# Connectors.net
KiCad netlist of a schematic drawn in Altium Designer
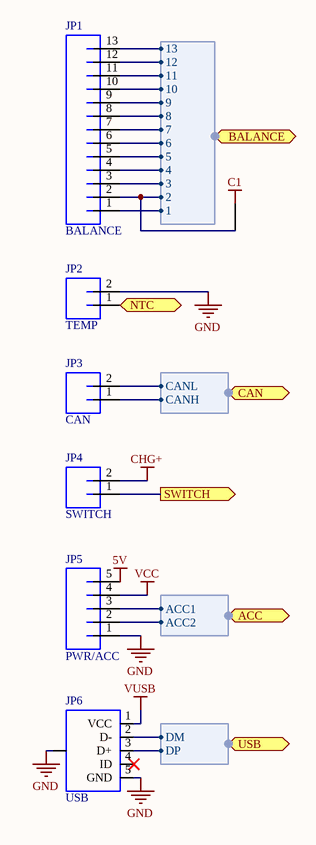
[diagram p0: Connectors.SchDoc]

(export (version "E")
  (design (tool "Eeschema 10.0.6"))
  (components
    (comp (ref "*1") (value "NetTie") (footprint "NetTie") (libsource (lib "Components") (part "NetTie")))
    (comp (ref "JP1")
      (value "BALANCE")
      (footprint "JST-XH-13-PTH-VERT")
      (fields
        (field (name "MANUFACTURER") "JST Sales America, Inc.")
        (field (name "PARTNUMBER") "B13B-XH-A(LF)(SN)")
      )
      (libsource (lib "Connectors-JST") (part "JST_XH_13_VERT"))
    )
    (comp (ref "JP2")
      (value "TEMP")
      (footprint "JST-PH-2-PTH-VERT")
      (fields
        (field (name "MANUFACTURER") "JST Sales America, Inc.")
        (field (name "PARTNUMBER") "B2B-PH-K-S(LF)(SN)")
      )
      (libsource (lib "Connectors") (part "JST_PH_2_VERT"))
    )
    (comp (ref "JP3")
      (value "CAN")
      (footprint "JST-PH-2-PTH-VERT")
      (fields
        (field (name "MANUFACTURER") "JST Sales America, Inc.")
        (field (name "PARTNUMBER") "B2B-PH-K-S(LF)(SN)")
      )
      (libsource (lib "Connectors") (part "JST_PH_2_VERT"))
    )
    (comp (ref "JP4")
      (value "SWITCH")
      (footprint "JST-PH-2-PTH-VERT")
      (fields
        (field (name "MANUFACTURER") "JST Sales America, Inc.")
        (field (name "PARTNUMBER") "B2B-PH-K-S(LF)(SN)")
      )
      (libsource (lib "Connectors") (part "JST_PH_2_VERT"))
    )
    (comp (ref "JP5")
      (value "PWR/ACC")
      (footprint "JST-PH-5-PTH-VERT")
      (fields
        (field (name "MANUFACTURER") "JST Sales America, Inc.")
        (field (name "PARTNUMBER") "B5B-PH-K-S(LF)(SN)")
      )
      (libsource (lib "Connectors") (part "JST_PH_5_VERT"))
    )
    (comp (ref "JP6")
      (value "USB")
      (footprint "USB-MICROB")
      (fields (field (name "PARTNUMBER") "10118192-0001LF") (field (name "MANUFACTURER") "Amphenol FCI"))
      (libsource (lib "Connectors") (part "USB_MICROB_SMT"))
    )
  )
  (nets
    (net (code "7") (name "/1") (class "Default")
      (node (ref "JP1") (pin "1") (pinfunction "1_1") (pintype "passive"))
    )
    (net (code "8") (name "/2") (class "Default")
      (node (ref "*1") (pin "1") (pinfunction "1_1") (pintype "passive"))
      (node (ref "JP1") (pin "2") (pinfunction "2_2") (pintype "passive"))
    )
    (net (code "9") (name "/3") (class "Default")
      (node (ref "JP1") (pin "3") (pinfunction "3_3") (pintype "passive"))
    )
    (net (code "10") (name "/4") (class "Default")
      (node (ref "JP1") (pin "4") (pinfunction "4_4") (pintype "passive"))
    )
    (net (code "11") (name "/5") (class "Default")
      (node (ref "JP1") (pin "5") (pinfunction "5_5") (pintype "passive"))
    )
    (net (code "12") (name "/6") (class "Default")
      (node (ref "JP1") (pin "6") (pinfunction "6_6") (pintype "passive"))
    )
    (net (code "13") (name "/7") (class "Default")
      (node (ref "JP1") (pin "7") (pinfunction "7_7") (pintype "passive"))
    )
    (net (code "14") (name "/8") (class "Default")
      (node (ref "JP1") (pin "8") (pinfunction "8_8") (pintype "passive"))
    )
    (net (code "15") (name "/9") (class "Default")
      (node (ref "JP1") (pin "9") (pinfunction "9_9") (pintype "passive"))
    )
    (net (code "16") (name "/10") (class "Default")
      (node (ref "JP1") (pin "10") (pinfunction "10_10") (pintype "passive"))
    )
    (net (code "17") (name "/11") (class "Default")
      (node (ref "JP1") (pin "11") (pinfunction "11_11") (pintype "passive"))
    )
    (net (code "18") (name "/12") (class "Default")
      (node (ref "JP1") (pin "12") (pinfunction "12_12") (pintype "passive"))
    )
    (net (code "19") (name "/13") (class "Default")
      (node (ref "JP1") (pin "13") (pinfunction "13_13") (pintype "passive"))
    )
    (net (code "20") (name "/ACC1") (class "Default")
      (node (ref "JP5") (pin "3") (pinfunction "3_3") (pintype "passive"))
    )
    (net (code "21") (name "/ACC2") (class "Default")
      (node (ref "JP5") (pin "2") (pinfunction "2_2") (pintype "passive"))
    )
    (net (code "22") (name "/CANH") (class "Default")
      (node (ref "JP3") (pin "1") (pinfunction "1_1") (pintype "passive"))
    )
    (net (code "23") (name "/CANL") (class "Default")
      (node (ref "JP3") (pin "2") (pinfunction "2_2") (pintype "passive"))
    )
    (net (code "24") (name "/DM") (class "Default")
      (node (ref "JP6") (pin "2") (pinfunction "D-_2") (pintype "passive"))
    )
    (net (code "25") (name "/DP") (class "Default")
      (node (ref "JP6") (pin "3") (pinfunction "D+_3") (pintype "passive"))
    )
    (net (code "26") (name "/NTC") (class "Default")
      (node (ref "JP2") (pin "1") (pinfunction "1_1") (pintype "passive"))
    )
    (net (code "27") (name "/SWITCH") (class "Default")
      (node (ref "JP4") (pin "1") (pinfunction "1_1") (pintype "passive"))
    )
    (net (code "32") (name "5V") (class "Default")
      (node (ref "JP5") (pin "5") (pinfunction "5_5") (pintype "passive"))
    )
    (net (code "33") (name "C1") (class "Default")
      (node (ref "*1") (pin "2") (pinfunction "2_2") (pintype "passive"))
    )
    (net (code "34") (name "CHG+") (class "Default")
      (node (ref "JP4") (pin "2") (pinfunction "2_2") (pintype "passive"))
    )
    (net (code "35") (name "GND") (class "Default")
      (node (ref "JP2") (pin "2") (pinfunction "2_2") (pintype "passive"))
      (node (ref "JP5") (pin "1") (pinfunction "1_1") (pintype "passive"))
      (node (ref "JP6") (pin "5") (pinfunction "GND_5") (pintype "passive"))
      (node (ref "JP6") (pin "6") (pinfunction "SHIELD_6") (pintype "passive"))
    )
    (net (code "36") (name "VCC") (class "Default")
      (node (ref "JP5") (pin "4") (pinfunction "4_4") (pintype "passive"))
    )
    (net (code "37") (name "VUSB") (class "Default")
      (node (ref "JP6") (pin "1") (pinfunction "VCC_1") (pintype "passive"))
    )
    (net (code "38") (name "unconnected-(JP6-ID-Pad4)") (class "Default")
      (node (ref "JP6") (pin "4") (pinfunction "ID_4") (pintype "passive+no_connect"))
    )
  )
)
